# mainboard.net
KiCad netlist of a schematic drawn in EAGLE
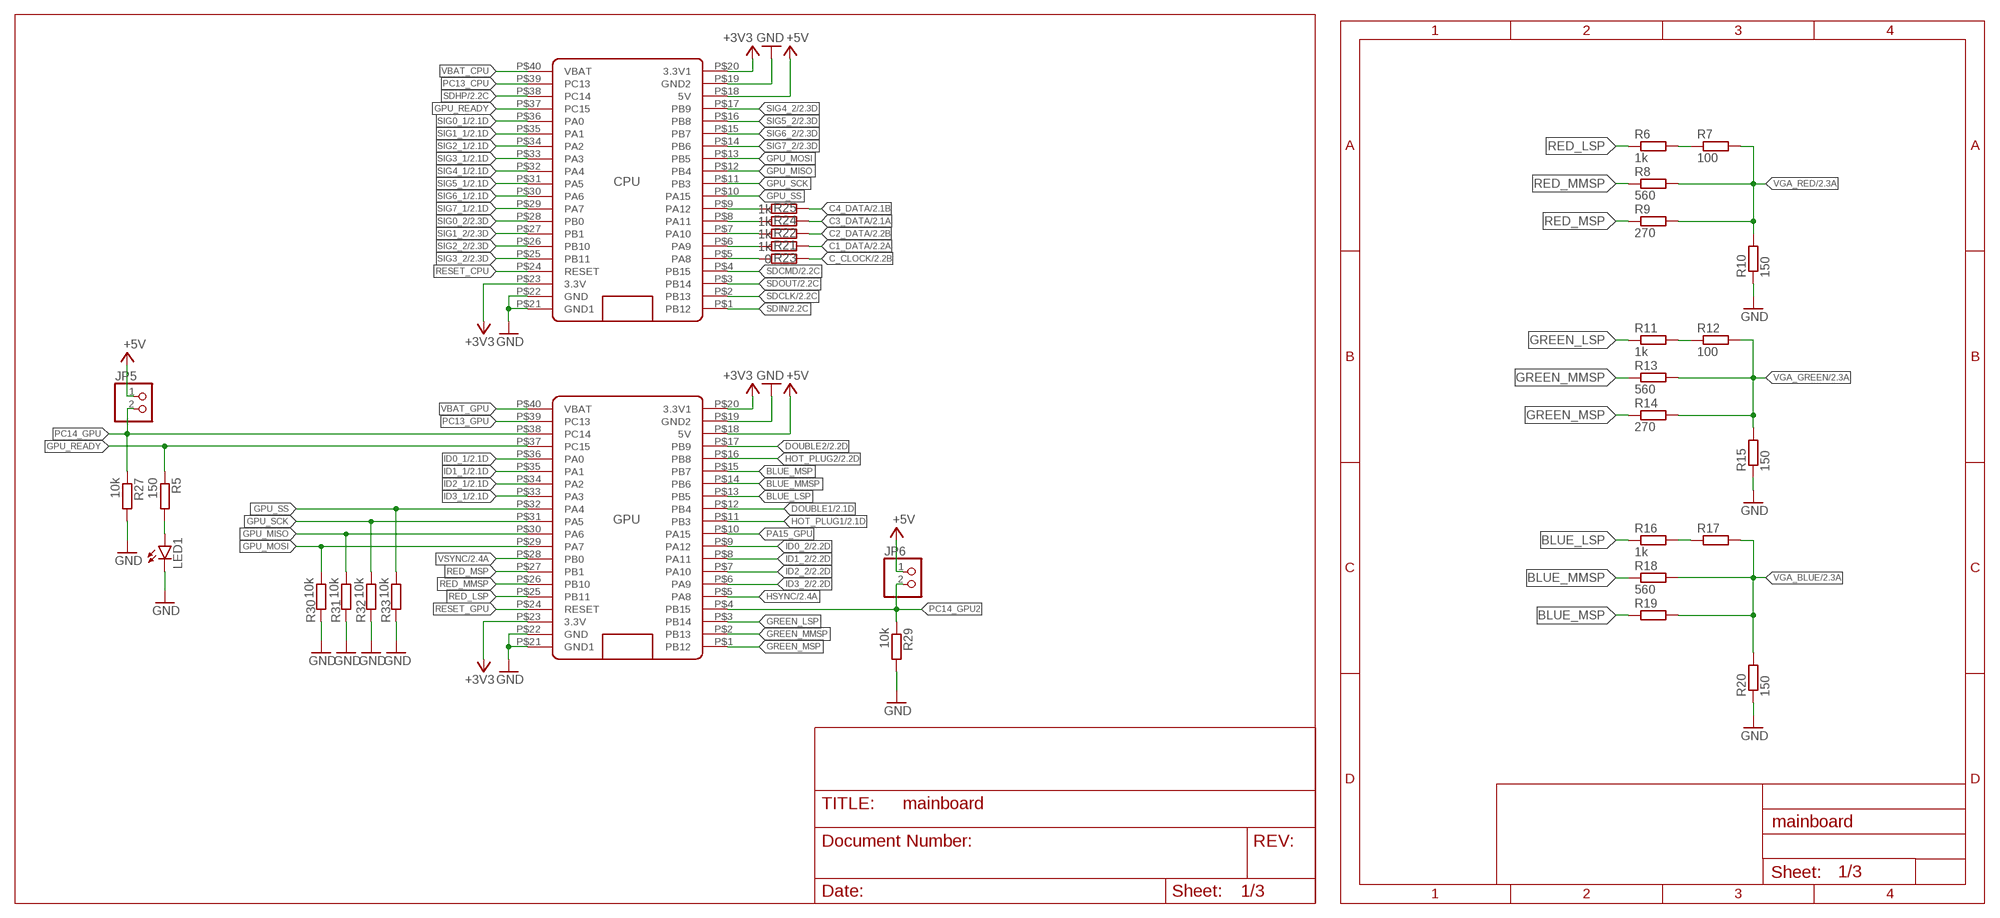
[diagram p0: schematic, sheet 1]
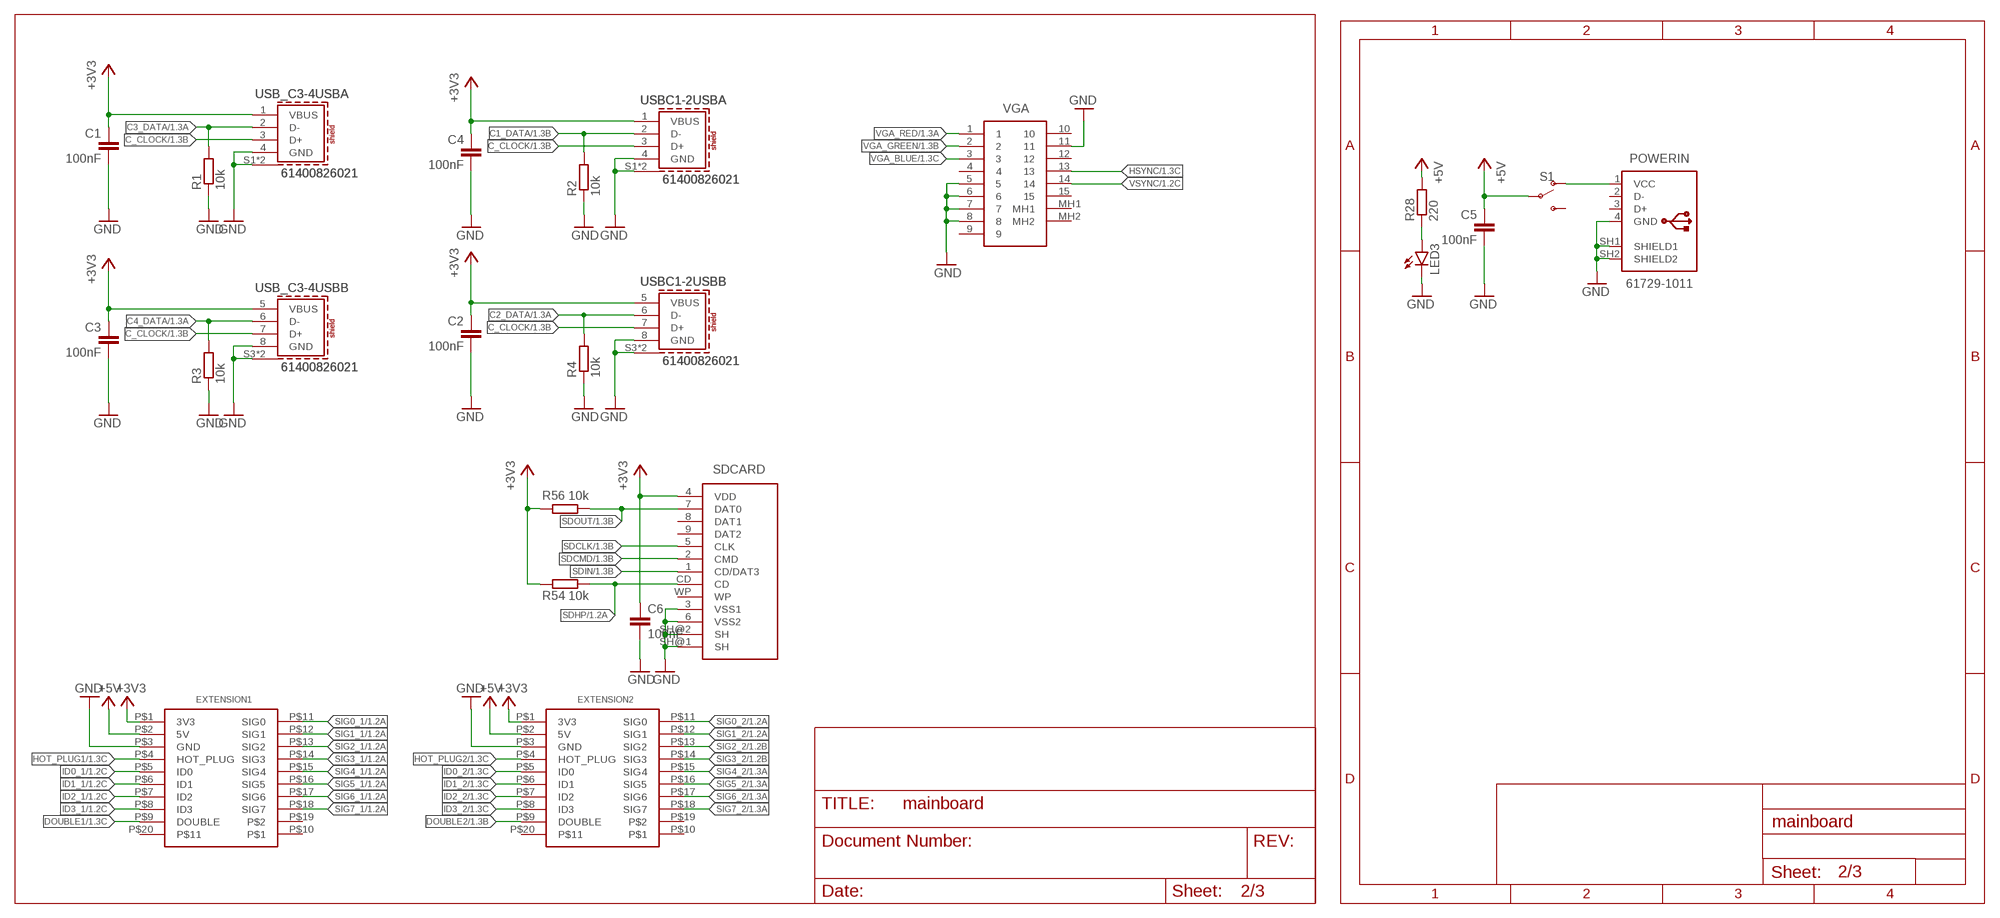
[diagram p1: schematic, sheet 2]
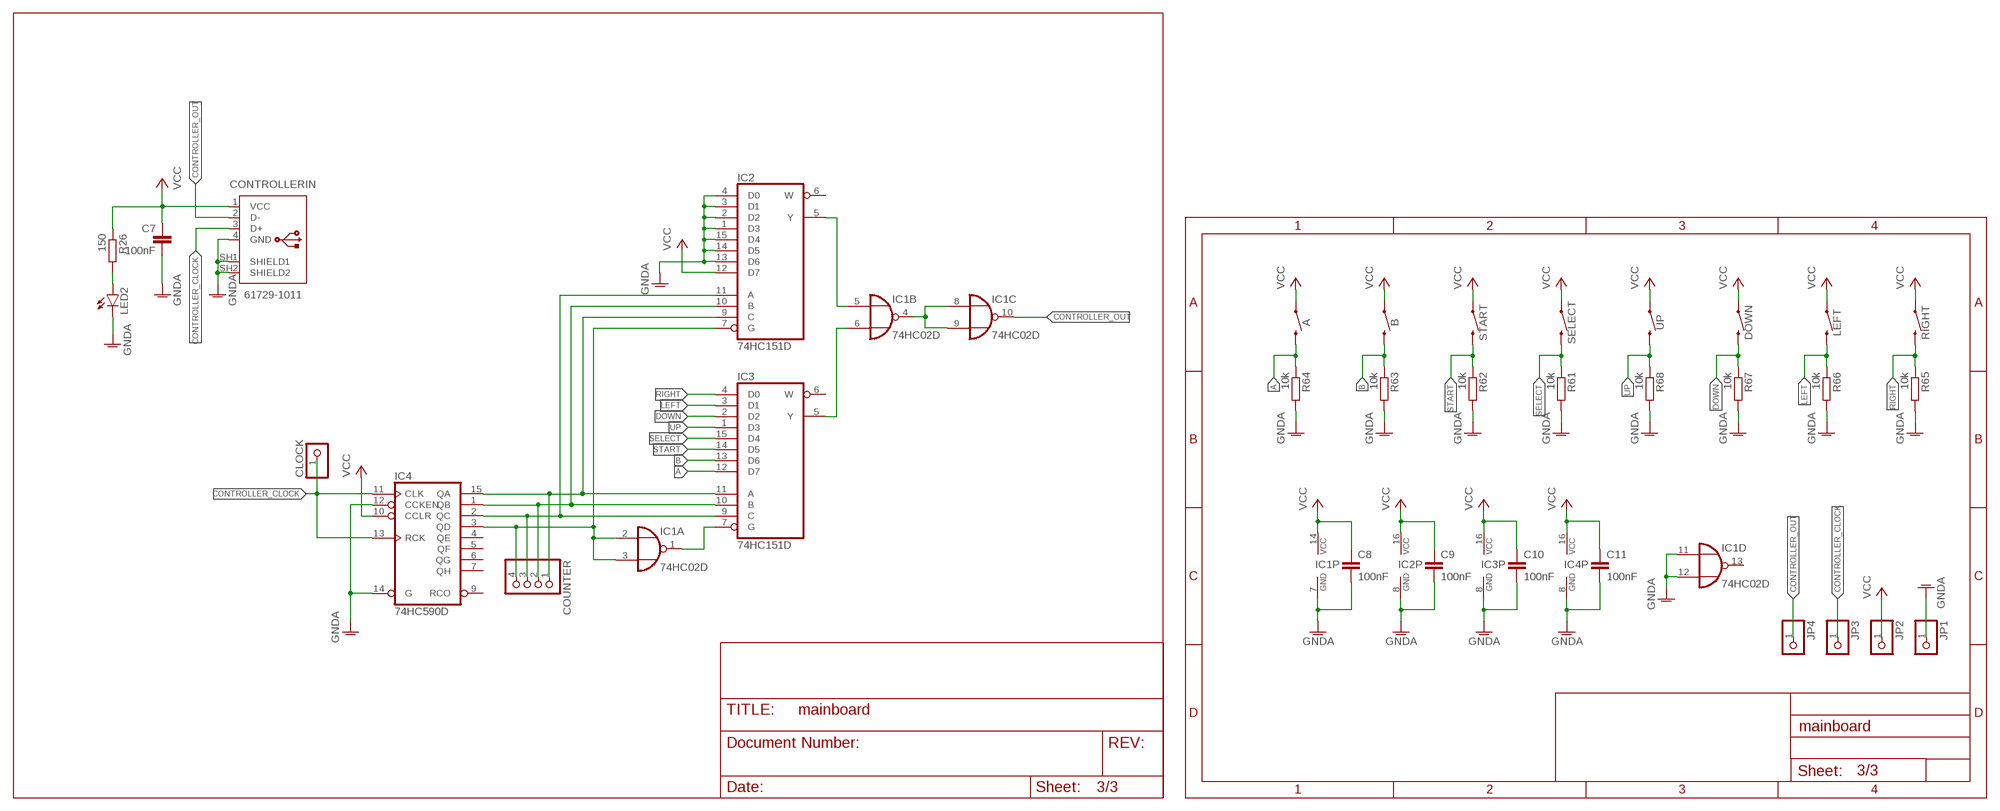
[diagram p2: schematic, sheet 3]

(export (version "E")
  (design (tool "Eeschema 10.0.6"))
  (components
    (comp (ref "C1")
      (value "100nF")
      (footprint "eagle-import:C0805")
      (libsource (lib "eagle-import") (part "C-EUC0805"))
    )
    (comp (ref "C2")
      (value "100nF")
      (footprint "eagle-import:C0805")
      (libsource (lib "eagle-import") (part "C-EUC0805"))
    )
    (comp (ref "C3")
      (value "100nF")
      (footprint "eagle-import:C0805")
      (libsource (lib "eagle-import") (part "C-EUC0805"))
    )
    (comp (ref "C4")
      (value "100nF")
      (footprint "eagle-import:C0805")
      (libsource (lib "eagle-import") (part "C-EUC0805"))
    )
    (comp (ref "C5")
      (value "100nF")
      (footprint "eagle-import:C0805")
      (libsource (lib "eagle-import") (part "C-EUC0805"))
    )
    (comp (ref "C6")
      (value "100nF")
      (footprint "eagle-import:C0805")
      (libsource (lib "eagle-import") (part "C-EUC0805"))
    )
    (comp (ref "EXTENSION1")
      (value "3511220BMSS0BNA1_2.54MM_2X20_MALE")
      (footprint "eagle-import:3511220BMSS0BNA1_2.54MM_2X20_MALE")
      (libsource (lib "eagle-import") (part "3511220BMSS0BNA1_2.54MM_2X20_MALE"))
    )
    (comp (ref "EXTENSION2")
      (value "3511220BMSS0BNA1_2.54MM_2X20_MALE")
      (footprint "eagle-import:3511220BMSS0BNA1_2.54MM_2X20_MALE")
      (libsource (lib "eagle-import") (part "3511220BMSS0BNA1_2.54MM_2X20_MALE"))
    )
    (comp (ref "LED3")
      (value "LEDCHIPLED_0805")
      (footprint "eagle-import:CHIPLED_0805")
      (libsource (lib "eagle-import") (part "LEDCHIPLED_0805"))
    )
    (comp (ref "POWERIN")
      (value "61729-1011")
      (footprint "eagle-import:61729-1011BLF")
      (fields (field (name "MANUFACTURER") "Amphenol ICC (FCI)") (field (name "MPN") "61729-1011BLF"))
      (libsource (lib "eagle-import") (part "61729-1011"))
    )
    (comp (ref "R1")
      (value "10k")
      (footprint "eagle-import:R0805")
      (libsource (lib "eagle-import") (part "R-EU_R0805"))
    )
    (comp (ref "R2")
      (value "10k")
      (footprint "eagle-import:R0805")
      (libsource (lib "eagle-import") (part "R-EU_R0805"))
    )
    (comp (ref "R3")
      (value "10k")
      (footprint "eagle-import:R0805")
      (libsource (lib "eagle-import") (part "R-EU_R0805"))
    )
    (comp (ref "R4")
      (value "10k")
      (footprint "eagle-import:R0805")
      (libsource (lib "eagle-import") (part "R-EU_R0805"))
    )
    (comp (ref "R28")
      (value "220")
      (footprint "eagle-import:R0805")
      (libsource (lib "eagle-import") (part "R-EU_R0805"))
    )
    (comp (ref "R54")
      (value "10k")
      (footprint "eagle-import:R0805")
      (libsource (lib "eagle-import") (part "R-EU_R0805"))
    )
    (comp (ref "R56")
      (value "10k")
      (footprint "eagle-import:R0805")
      (libsource (lib "eagle-import") (part "R-EU_R0805"))
    )
    (comp (ref "S1")
      (value "SWITCH-SPDT-PTH-11.6X4.0MM")
      (footprint "eagle-import:SWITCH_SPDT_PTH_11.6X4.0MM")
      (libsource (lib "eagle-import") (part "SWITCH-SPDT-PTH-11.6X4.0MM"))
    )
    (comp (ref "SD-CARD")
      (value "SD_CARD_SOCKET")
      (footprint "eagle-import:SD")
      (libsource (lib "eagle-import") (part "SD_CARD_SOCKET"))
    )
    (comp (ref "USBC1-2")
      (value "61400826021")
      (footprint "eagle-import:61400826021")
      (libsource (lib "eagle-import") (part "61400826021"))
    )
    (comp (ref "USB_C3-4")
      (value "61400826021")
      (footprint "eagle-import:61400826021")
      (libsource (lib "eagle-import") (part "61400826021"))
    )
    (comp (ref "VGA")
      (value "L77HDE15SD1CH4RHNVGA")
      (footprint "eagle-import:L77HDE15SD1CH4RHNVGA")
      (fields (field (name "MOUSER_PART_NUMBER") "523-7HDE15SDH4RHNVGA"))
      (libsource (lib "eagle-import") (part "L77HDE15SD1CH4RHNVGA"))
    )
    (comp (ref "A")
      (value "MOMENTARY-SWITCH-SPST-PTH-12MM")
      (footprint "eagle-import:TACTILE_SWITCH_PTH_12MM")
      (libsource (lib "eagle-import") (part "MOMENTARY-SWITCH-SPST-PTH-12MM"))
    )
    (comp (ref "B")
      (value "MOMENTARY-SWITCH-SPST-PTH-12MM")
      (footprint "eagle-import:TACTILE_SWITCH_PTH_12MM")
      (libsource (lib "eagle-import") (part "MOMENTARY-SWITCH-SPST-PTH-12MM"))
    )
    (comp (ref "C7")
      (value "100nF")
      (footprint "eagle-import:C0805")
      (libsource (lib "eagle-import") (part "C-EUC0805"))
    )
    (comp (ref "C8")
      (value "100nF")
      (footprint "eagle-import:C0805")
      (libsource (lib "eagle-import") (part "C-EUC0805"))
    )
    (comp (ref "C9")
      (value "100nF")
      (footprint "eagle-import:C0805")
      (libsource (lib "eagle-import") (part "C-EUC0805"))
    )
    (comp (ref "C10")
      (value "100nF")
      (footprint "eagle-import:C0805")
      (libsource (lib "eagle-import") (part "C-EUC0805"))
    )
    (comp (ref "C11")
      (value "100nF")
      (footprint "eagle-import:C0805")
      (libsource (lib "eagle-import") (part "C-EUC0805"))
    )
    (comp (ref "CLOCK")
      (value "PINHD-1X1")
      (footprint "eagle-import:1X01")
      (libsource (lib "eagle-import") (part "PINHD-1X1"))
    )
    (comp (ref "CONTROLLERIN")
      (value "61729-1011")
      (footprint "eagle-import:61729-1011BLF")
      (fields (field (name "MANUFACTURER") "Amphenol ICC (FCI)") (field (name "MPN") "61729-1011BLF"))
      (libsource (lib "eagle-import") (part "61729-1011"))
    )
    (comp (ref "COUNTER")
      (value "PINHD-1X4")
      (footprint "eagle-import:1X04")
      (libsource (lib "eagle-import") (part "PINHD-1X4"))
    )
    (comp (ref "DOWN")
      (value "MOMENTARY-SWITCH-SPST-PTH-12MM")
      (footprint "eagle-import:TACTILE_SWITCH_PTH_12MM")
      (libsource (lib "eagle-import") (part "MOMENTARY-SWITCH-SPST-PTH-12MM"))
    )
    (comp (ref "IC1")
      (value "74HC02D")
      (footprint "eagle-import:SO14")
      (libsource (lib "eagle-import") (part "7402DHC"))
    )
    (comp (ref "IC2")
      (value "74HC151D")
      (footprint "eagle-import:SO16")
      (libsource (lib "eagle-import") (part "74151DHC"))
    )
    (comp (ref "IC3")
      (value "74HC151D")
      (footprint "eagle-import:SO16")
      (libsource (lib "eagle-import") (part "74151DHC"))
    )
    (comp (ref "IC4")
      (value "74HC590D")
      (footprint "eagle-import:SO16")
      (libsource (lib "eagle-import") (part "74590DHC"))
    )
    (comp (ref "JP1")
      (value "PINHD-1X1")
      (footprint "eagle-import:1X01")
      (libsource (lib "eagle-import") (part "PINHD-1X1"))
    )
    (comp (ref "JP2")
      (value "PINHD-1X1")
      (footprint "eagle-import:1X01")
      (libsource (lib "eagle-import") (part "PINHD-1X1"))
    )
    (comp (ref "JP3")
      (value "PINHD-1X1")
      (footprint "eagle-import:1X01")
      (libsource (lib "eagle-import") (part "PINHD-1X1"))
    )
    (comp (ref "JP4")
      (value "PINHD-1X1")
      (footprint "eagle-import:1X01")
      (libsource (lib "eagle-import") (part "PINHD-1X1"))
    )
    (comp (ref "LED2")
      (value "LEDCHIPLED_0805")
      (footprint "eagle-import:CHIPLED_0805")
      (libsource (lib "eagle-import") (part "LEDCHIPLED_0805"))
    )
    (comp (ref "LEFT")
      (value "MOMENTARY-SWITCH-SPST-PTH-12MM")
      (footprint "eagle-import:TACTILE_SWITCH_PTH_12MM")
      (libsource (lib "eagle-import") (part "MOMENTARY-SWITCH-SPST-PTH-12MM"))
    )
    (comp (ref "R26")
      (value "150")
      (footprint "eagle-import:R0805")
      (libsource (lib "eagle-import") (part "R-EU_R0805"))
    )
    (comp (ref "R61")
      (value "10k")
      (footprint "eagle-import:R0805")
      (libsource (lib "eagle-import") (part "R-EU_R0805"))
    )
    (comp (ref "R62")
      (value "10k")
      (footprint "eagle-import:R0805")
      (libsource (lib "eagle-import") (part "R-EU_R0805"))
    )
    (comp (ref "R63")
      (value "10k")
      (footprint "eagle-import:R0805")
      (libsource (lib "eagle-import") (part "R-EU_R0805"))
    )
    (comp (ref "R64")
      (value "10k")
      (footprint "eagle-import:R0805")
      (libsource (lib "eagle-import") (part "R-EU_R0805"))
    )
    (comp (ref "R65")
      (value "10k")
      (footprint "eagle-import:R0805")
      (libsource (lib "eagle-import") (part "R-EU_R0805"))
    )
    (comp (ref "R66")
      (value "10k")
      (footprint "eagle-import:R0805")
      (libsource (lib "eagle-import") (part "R-EU_R0805"))
    )
    (comp (ref "R67")
      (value "10k")
      (footprint "eagle-import:R0805")
      (libsource (lib "eagle-import") (part "R-EU_R0805"))
    )
    (comp (ref "R68")
      (value "10k")
      (footprint "eagle-import:R0805")
      (libsource (lib "eagle-import") (part "R-EU_R0805"))
    )
    (comp (ref "RIGHT")
      (value "MOMENTARY-SWITCH-SPST-PTH-12MM")
      (footprint "eagle-import:TACTILE_SWITCH_PTH_12MM")
      (libsource (lib "eagle-import") (part "MOMENTARY-SWITCH-SPST-PTH-12MM"))
    )
    (comp (ref "SELECT")
      (value "MOMENTARY-SWITCH-SPST-PTH-12MM")
      (footprint "eagle-import:TACTILE_SWITCH_PTH_12MM")
      (libsource (lib "eagle-import") (part "MOMENTARY-SWITCH-SPST-PTH-12MM"))
    )
    (comp (ref "START")
      (value "MOMENTARY-SWITCH-SPST-PTH-12MM")
      (footprint "eagle-import:TACTILE_SWITCH_PTH_12MM")
      (libsource (lib "eagle-import") (part "MOMENTARY-SWITCH-SPST-PTH-12MM"))
    )
    (comp (ref "UP")
      (value "MOMENTARY-SWITCH-SPST-PTH-12MM")
      (footprint "eagle-import:TACTILE_SWITCH_PTH_12MM")
      (libsource (lib "eagle-import") (part "MOMENTARY-SWITCH-SPST-PTH-12MM"))
    )
    (comp (ref "CPU")
      (value "BLUE_PILLADVANCED")
      (footprint "eagle-import:BLUE_PILL_ADV")
      (libsource (lib "eagle-import") (part "BLUE_PILLADVANCED"))
    )
    (comp (ref "GPU")
      (value "BLUE_PILLADVANCED")
      (footprint "eagle-import:BLUE_PILL_ADV")
      (libsource (lib "eagle-import") (part "BLUE_PILLADVANCED"))
    )
    (comp (ref "JP5")
      (value "PINHD-1X2")
      (footprint "eagle-import:1X02")
      (libsource (lib "eagle-import") (part "PINHD-1X2"))
    )
    (comp (ref "JP6")
      (value "PINHD-1X2")
      (footprint "eagle-import:1X02")
      (libsource (lib "eagle-import") (part "PINHD-1X2"))
    )
    (comp (ref "LED1")
      (value "LEDCHIPLED_0805")
      (footprint "eagle-import:CHIPLED_0805")
      (libsource (lib "eagle-import") (part "LEDCHIPLED_0805"))
    )
    (comp (ref "R5")
      (value "150")
      (footprint "eagle-import:R0805")
      (libsource (lib "eagle-import") (part "R-EU_R0805"))
    )
    (comp (ref "R6")
      (value "1k")
      (footprint "eagle-import:R0805")
      (libsource (lib "eagle-import") (part "R-EU_R0805"))
    )
    (comp (ref "R7")
      (value "100")
      (footprint "eagle-import:R0805")
      (libsource (lib "eagle-import") (part "R-EU_R0805"))
    )
    (comp (ref "R8")
      (value "560")
      (footprint "eagle-import:R0805")
      (libsource (lib "eagle-import") (part "R-EU_R0805"))
    )
    (comp (ref "R9")
      (value "270")
      (footprint "eagle-import:R0805")
      (libsource (lib "eagle-import") (part "R-EU_R0805"))
    )
    (comp (ref "R10")
      (value "150")
      (footprint "eagle-import:R0805")
      (libsource (lib "eagle-import") (part "R-EU_R0805"))
    )
    (comp (ref "R11")
      (value "1k")
      (footprint "eagle-import:R0805")
      (libsource (lib "eagle-import") (part "R-EU_R0805"))
    )
    (comp (ref "R12")
      (value "100")
      (footprint "eagle-import:R0805")
      (libsource (lib "eagle-import") (part "R-EU_R0805"))
    )
    (comp (ref "R13")
      (value "560")
      (footprint "eagle-import:R0805")
      (libsource (lib "eagle-import") (part "R-EU_R0805"))
    )
    (comp (ref "R14")
      (value "270")
      (footprint "eagle-import:R0805")
      (libsource (lib "eagle-import") (part "R-EU_R0805"))
    )
    (comp (ref "R15")
      (value "150")
      (footprint "eagle-import:R0805")
      (libsource (lib "eagle-import") (part "R-EU_R0805"))
    )
    (comp (ref "R16")
      (value "1k")
      (footprint "eagle-import:R0805")
      (libsource (lib "eagle-import") (part "R-EU_R0805"))
    )
    (comp (ref "R17")
      (value "100")
      (footprint "eagle-import:R0805")
      (libsource (lib "eagle-import") (part "R-EU_R0805"))
    )
    (comp (ref "R18")
      (value "560")
      (footprint "eagle-import:R0805")
      (libsource (lib "eagle-import") (part "R-EU_R0805"))
    )
    (comp (ref "R19")
      (value "270")
      (footprint "eagle-import:R0805")
      (libsource (lib "eagle-import") (part "R-EU_R0805"))
    )
    (comp (ref "R20")
      (value "150")
      (footprint "eagle-import:R0805")
      (libsource (lib "eagle-import") (part "R-EU_R0805"))
    )
    (comp (ref "R21")
      (value "1k")
      (footprint "eagle-import:R0805")
      (libsource (lib "eagle-import") (part "R-EU_R0805"))
    )
    (comp (ref "R22")
      (value "1k")
      (footprint "eagle-import:R0805")
      (libsource (lib "eagle-import") (part "R-EU_R0805"))
    )
    (comp (ref "R23")
      (value "0")
      (footprint "eagle-import:R0805")
      (libsource (lib "eagle-import") (part "R-EU_R0805"))
    )
    (comp (ref "R24")
      (value "1k")
      (footprint "eagle-import:R0805")
      (libsource (lib "eagle-import") (part "R-EU_R0805"))
    )
    (comp (ref "R25")
      (value "1k")
      (footprint "eagle-import:R0805")
      (libsource (lib "eagle-import") (part "R-EU_R0805"))
    )
    (comp (ref "R27")
      (value "10k")
      (footprint "eagle-import:R0805")
      (libsource (lib "eagle-import") (part "R-EU_R0805"))
    )
    (comp (ref "R29")
      (value "10k")
      (footprint "eagle-import:R0805")
      (libsource (lib "eagle-import") (part "R-EU_R0805"))
    )
    (comp (ref "R30")
      (value "10k")
      (footprint "eagle-import:R0805")
      (libsource (lib "eagle-import") (part "R-EU_R0805"))
    )
    (comp (ref "R31")
      (value "10k")
      (footprint "eagle-import:R0805")
      (libsource (lib "eagle-import") (part "R-EU_R0805"))
    )
    (comp (ref "R32")
      (value "10k")
      (footprint "eagle-import:R0805")
      (libsource (lib "eagle-import") (part "R-EU_R0805"))
    )
    (comp (ref "R33")
      (value "10k")
      (footprint "eagle-import:R0805")
      (libsource (lib "eagle-import") (part "R-EU_R0805"))
    )
  )
  (nets
    (net (code "1") (name "+3V3") (class "Default")
      (node (ref "C1") (pin "1") (pinfunction "1_1") (pintype "passive"))
      (node (ref "C2") (pin "1") (pinfunction "1_1") (pintype "passive"))
      (node (ref "C3") (pin "1") (pinfunction "1_1") (pintype "passive"))
      (node (ref "C4") (pin "1") (pinfunction "1_1") (pintype "passive"))
      (node (ref "C6") (pin "1") (pinfunction "1_1") (pintype "passive"))
      (node (ref "CPU") (pin "P$20") (pinfunction "3.3V1_P$20") (pintype "bidirectional"))
      (node (ref "CPU") (pin "P$23") (pinfunction "3.3V_P$23") (pintype "bidirectional"))
      (node (ref "EXTENSION1") (pin "P$1") (pinfunction "3V3_P$1") (pintype "bidirectional"))
      (node (ref "EXTENSION2") (pin "P$1") (pinfunction "3V3_P$1") (pintype "bidirectional"))
      (node (ref "GPU") (pin "P$20") (pinfunction "3.3V1_P$20") (pintype "bidirectional"))
      (node (ref "GPU") (pin "P$23") (pinfunction "3.3V_P$23") (pintype "bidirectional"))
      (node (ref "R54") (pin "2") (pinfunction "2_2") (pintype "passive"))
      (node (ref "R56") (pin "2") (pinfunction "2_2") (pintype "passive"))
      (node (ref "SD-CARD") (pin "4") (pinfunction "VDD_4") (pintype "power_in"))
      (node (ref "USBC1-2") (pin "1") (pinfunction "VBUS_1") (pintype "passive"))
      (node (ref "USBC1-2") (pin "5") (pinfunction "VBUS_5") (pintype "passive"))
      (node (ref "USB_C3-4") (pin "1") (pinfunction "VBUS_1") (pintype "passive"))
      (node (ref "USB_C3-4") (pin "5") (pinfunction "VBUS_5") (pintype "passive"))
    )
    (net (code "2") (name "+5V") (class "Default")
      (node (ref "C5") (pin "1") (pinfunction "1_1") (pintype "passive"))
      (node (ref "CPU") (pin "P$18") (pinfunction "5V_P$18") (pintype "bidirectional"))
      (node (ref "EXTENSION1") (pin "P$2") (pinfunction "5V_P$2") (pintype "bidirectional"))
      (node (ref "EXTENSION2") (pin "P$2") (pinfunction "5V_P$2") (pintype "bidirectional"))
      (node (ref "GPU") (pin "P$18") (pinfunction "5V_P$18") (pintype "bidirectional"))
      (node (ref "JP5") (pin "1") (pinfunction "1_1") (pintype "passive"))
      (node (ref "JP6") (pin "1") (pinfunction "1_1") (pintype "passive"))
      (node (ref "R28") (pin "2") (pinfunction "2_2") (pintype "passive"))
      (node (ref "S1") (pin "2") (pinfunction "P_2") (pintype "passive"))
    )
    (net (code "3") (name "A") (class "Default")
      (node (ref "A") (pin "3") (pinfunction "2_3") (pintype "passive"))
      (node (ref "IC3") (pin "12") (pinfunction "D7_12") (pintype "input"))
      (node (ref "R64") (pin "1") (pinfunction "1_1") (pintype "passive"))
    )
    (net (code "4") (name "B") (class "Default")
      (node (ref "B") (pin "3") (pinfunction "2_3") (pintype "passive"))
      (node (ref "IC3") (pin "13") (pinfunction "D6_13") (pintype "input"))
      (node (ref "R63") (pin "1") (pinfunction "1_1") (pintype "passive"))
    )
    (net (code "5") (name "BLUE_LSP") (class "Default")
      (node (ref "GPU") (pin "P$13") (pinfunction "PB5_P$13") (pintype "bidirectional"))
      (node (ref "R16") (pin "1") (pinfunction "1_1") (pintype "passive"))
    )
    (net (code "6") (name "BLUE_MMSP") (class "Default")
      (node (ref "GPU") (pin "P$14") (pinfunction "PB6_P$14") (pintype "bidirectional"))
      (node (ref "R18") (pin "1") (pinfunction "1_1") (pintype "passive"))
    )
    (net (code "7") (name "BLUE_MSP") (class "Default")
      (node (ref "GPU") (pin "P$15") (pinfunction "PB7_P$15") (pintype "bidirectional"))
      (node (ref "R19") (pin "1") (pinfunction "1_1") (pintype "passive"))
    )
    (net (code "8") (name "C1_DATA") (class "Default")
      (node (ref "R2") (pin "2") (pinfunction "2_2") (pintype "passive"))
      (node (ref "R21") (pin "1") (pinfunction "1_1") (pintype "passive"))
      (node (ref "USBC1-2") (pin "2") (pinfunction "D-_2") (pintype "passive"))
    )
    (net (code "9") (name "C2_DATA") (class "Default")
      (node (ref "R22") (pin "1") (pinfunction "1_1") (pintype "passive"))
      (node (ref "R4") (pin "2") (pinfunction "2_2") (pintype "passive"))
      (node (ref "USBC1-2") (pin "6") (pinfunction "D-_6") (pintype "passive"))
    )
    (net (code "10") (name "C3_DATA") (class "Default")
      (node (ref "R1") (pin "2") (pinfunction "2_2") (pintype "passive"))
      (node (ref "R24") (pin "1") (pinfunction "1_1") (pintype "passive"))
      (node (ref "USB_C3-4") (pin "2") (pinfunction "D-_2") (pintype "passive"))
    )
    (net (code "11") (name "C4_DATA") (class "Default")
      (node (ref "R25") (pin "1") (pinfunction "1_1") (pintype "passive"))
      (node (ref "R3") (pin "2") (pinfunction "2_2") (pintype "passive"))
      (node (ref "USB_C3-4") (pin "6") (pinfunction "D-_6") (pintype "passive"))
    )
    (net (code "12") (name "CONTROLLER_CLOCK") (class "Default")
      (node (ref "CLOCK") (pin "1") (pinfunction "1_1") (pintype "passive"))
      (node (ref "CONTROLLERIN") (pin "3") (pinfunction "D+_3") (pintype "bidirectional"))
      (node (ref "IC4") (pin "11") (pinfunction "CLK_11") (pintype "input"))
      (node (ref "IC4") (pin "13") (pinfunction "RCK_13") (pintype "input"))
      (node (ref "JP3") (pin "1") (pinfunction "1_1") (pintype "passive"))
    )
    (net (code "13") (name "CONTROLLER_OUT") (class "Default")
      (node (ref "CONTROLLERIN") (pin "2") (pinfunction "D-_2") (pintype "bidirectional"))
      (node (ref "IC1") (pin "10") (pinfunction "O_10") (pintype "output"))
      (node (ref "JP4") (pin "1") (pinfunction "1_1") (pintype "passive"))
    )
    (net (code "14") (name "C_CLOCK") (class "Default")
      (node (ref "R23") (pin "1") (pinfunction "1_1") (pintype "passive"))
      (node (ref "USBC1-2") (pin "3") (pinfunction "D+_3") (pintype "passive"))
      (node (ref "USBC1-2") (pin "7") (pinfunction "D+_7") (pintype "passive"))
      (node (ref "USB_C3-4") (pin "3") (pinfunction "D+_3") (pintype "passive"))
      (node (ref "USB_C3-4") (pin "7") (pinfunction "D+_7") (pintype "passive"))
    )
    (net (code "15") (name "DOUBLE1") (class "Default")
      (node (ref "EXTENSION1") (pin "P$9") (pinfunction "DOUBLE_P$9") (pintype "bidirectional"))
      (node (ref "GPU") (pin "P$12") (pinfunction "PB4_P$12") (pintype "bidirectional"))
    )
    (net (code "16") (name "DOUBLE2") (class "Default")
      (node (ref "EXTENSION2") (pin "P$9") (pinfunction "DOUBLE_P$9") (pintype "bidirectional"))
      (node (ref "GPU") (pin "P$17") (pinfunction "PB9_P$17") (pintype "bidirectional"))
    )
    (net (code "17") (name "DOWN") (class "Default")
      (node (ref "DOWN") (pin "3") (pinfunction "2_3") (pintype "passive"))
      (node (ref "IC3") (pin "2") (pinfunction "D2_2") (pintype "input"))
      (node (ref "R67") (pin "1") (pinfunction "1_1") (pintype "passive"))
    )
    (net (code "18") (name "GND") (class "Default")
      (node (ref "C1") (pin "2") (pinfunction "2_2") (pintype "passive"))
      (node (ref "C2") (pin "2") (pinfunction "2_2") (pintype "passive"))
      (node (ref "C3") (pin "2") (pinfunction "2_2") (pintype "passive"))
      (node (ref "C4") (pin "2") (pinfunction "2_2") (pintype "passive"))
      (node (ref "C5") (pin "2") (pinfunction "2_2") (pintype "passive"))
      (node (ref "C6") (pin "2") (pinfunction "2_2") (pintype "passive"))
      (node (ref "CPU") (pin "P$19") (pinfunction "GND2_P$19") (pintype "bidirectional"))
      (node (ref "CPU") (pin "P$21") (pinfunction "GND1_P$21") (pintype "power_in"))
      (node (ref "CPU") (pin "P$22") (pinfunction "GND_P$22") (pintype "bidirectional"))
      (node (ref "EXTENSION1") (pin "P$3") (pinfunction "GND_P$3") (pintype "bidirectional"))
      (node (ref "EXTENSION2") (pin "P$3") (pinfunction "GND_P$3") (pintype "bidirectional"))
      (node (ref "GPU") (pin "P$19") (pinfunction "GND2_P$19") (pintype "bidirectional"))
      (node (ref "GPU") (pin "P$21") (pinfunction "GND1_P$21") (pintype "power_in"))
      (node (ref "GPU") (pin "P$22") (pinfunction "GND_P$22") (pintype "bidirectional"))
      (node (ref "LED1") (pin "C") (pinfunction "C_C") (pintype "passive"))
      (node (ref "LED3") (pin "C") (pinfunction "C_C") (pintype "passive"))
      (node (ref "POWERIN") (pin "4") (pinfunction "GND_4") (pintype "power_in"))
      (node (ref "POWERIN") (pin "SH1") (pinfunction "SHIELD1_SH1") (pintype "power_in"))
      (node (ref "POWERIN") (pin "SH2") (pinfunction "SHIELD2_SH2") (pintype "power_in"))
      (node (ref "R1") (pin "1") (pinfunction "1_1") (pintype "passive"))
      (node (ref "R10") (pin "1") (pinfunction "1_1") (pintype "passive"))
      (node (ref "R15") (pin "1") (pinfunction "1_1") (pintype "passive"))
      (node (ref "R2") (pin "1") (pinfunction "1_1") (pintype "passive"))
      (node (ref "R20") (pin "1") (pinfunction "1_1") (pintype "passive"))
      (node (ref "R27") (pin "2") (pinfunction "2_2") (pintype "passive"))
      (node (ref "R29") (pin "2") (pinfunction "2_2") (pintype "passive"))
      (node (ref "R3") (pin "1") (pinfunction "1_1") (pintype "passive"))
      (node (ref "R30") (pin "2") (pinfunction "2_2") (pintype "passive"))
      (node (ref "R31") (pin "2") (pinfunction "2_2") (pintype "passive"))
      (node (ref "R32") (pin "2") (pinfunction "2_2") (pintype "passive"))
      (node (ref "R33") (pin "2") (pinfunction "2_2") (pintype "passive"))
      (node (ref "R4") (pin "1") (pinfunction "1_1") (pintype "passive"))
      (node (ref "SD-CARD") (pin "3") (pinfunction "VSS1_3") (pintype "power_in"))
      (node (ref "SD-CARD") (pin "6") (pinfunction "VSS2_6") (pintype "power_in"))
      (node (ref "SD-CARD") (pin "SH@1") (pinfunction "SH_SH@1") (pintype "bidirectional"))
      (node (ref "SD-CARD") (pin "SH@2") (pinfunction "SH_SH@2") (pintype "bidirectional"))
      (node (ref "USBC1-2") (pin "4") (pinfunction "GND_4") (pintype "passive"))
      (node (ref "USBC1-2") (pin "8") (pinfunction "GND_8") (pintype "passive"))
      (node (ref "USBC1-2") (pin "S1") (pinfunction "SHIELD_S1") (pintype "passive"))
      (node (ref "USBC1-2") (pin "S2") (pinfunction "SHIELD_S2") (pintype "passive"))
      (node (ref "USBC1-2") (pin "S3") (pinfunction "SHIELD_S3") (pintype "passive"))
      (node (ref "USBC1-2") (pin "S4") (pinfunction "SHIELD_S4") (pintype "passive"))
      (node (ref "USB_C3-4") (pin "4") (pinfunction "GND_4") (pintype "passive"))
      (node (ref "USB_C3-4") (pin "8") (pinfunction "GND_8") (pintype "passive"))
      (node (ref "USB_C3-4") (pin "S1") (pinfunction "SHIELD_S1") (pintype "passive"))
      (node (ref "USB_C3-4") (pin "S2") (pinfunction "SHIELD_S2") (pintype "passive"))
      (node (ref "USB_C3-4") (pin "S3") (pinfunction "SHIELD_S3") (pintype "passive"))
      (node (ref "USB_C3-4") (pin "S4") (pinfunction "SHIELD_S4") (pintype "passive"))
      (node (ref "VGA") (pin "11") (pinfunction "11_11") (pintype "bidirectional"))
      (node (ref "VGA") (pin "5") (pinfunction "5_5") (pintype "bidirectional"))
      (node (ref "VGA") (pin "6") (pinfunction "6_6") (pintype "bidirectional"))
      (node (ref "VGA") (pin "7") (pinfunction "7_7") (pintype "bidirectional"))
      (node (ref "VGA") (pin "8") (pinfunction "8_8") (pintype "bidirectional"))
    )
    (net (code "19") (name "GNDA") (class "Default")
      (node (ref "C10") (pin "2") (pinfunction "2_2") (pintype "passive"))
      (node (ref "C11") (pin "2") (pinfunction "2_2") (pintype "passive"))
      (node (ref "C7") (pin "2") (pinfunction "2_2") (pintype "passive"))
      (node (ref "C8") (pin "2") (pinfunction "2_2") (pintype "passive"))
      (node (ref "C9") (pin "2") (pinfunction "2_2") (pintype "passive"))
      (node (ref "CONTROLLERIN") (pin "4") (pinfunction "GND_4") (pintype "power_in"))
      (node (ref "CONTROLLERIN") (pin "SH1") (pinfunction "SHIELD1_SH1") (pintype "power_in"))
      (node (ref "CONTROLLERIN") (pin "SH2") (pinfunction "SHIELD2_SH2") (pintype "power_in"))
      (node (ref "IC1") (pin "11") (pinfunction "I0_11") (pintype "input"))
      (node (ref "IC1") (pin "12") (pinfunction "I1_12") (pintype "input"))
      (node (ref "IC1") (pin "7") (pinfunction "GND_7") (pintype "power_in"))
      (node (ref "IC2") (pin "1") (pinfunction "D3_1") (pintype "input"))
      (node (ref "IC2") (pin "13") (pinfunction "D6_13") (pintype "input"))
      (node (ref "IC2") (pin "14") (pinfunction "D5_14") (pintype "input"))
      (node (ref "IC2") (pin "15") (pinfunction "D4_15") (pintype "input"))
      (node (ref "IC2") (pin "2") (pinfunction "D2_2") (pintype "input"))
      (node (ref "IC2") (pin "3") (pinfunction "D1_3") (pintype "input"))
      (node (ref "IC2") (pin "4") (pinfunction "D0_4") (pintype "input"))
      (node (ref "IC2") (pin "8") (pinfunction "GND_8") (pintype "power_in"))
      (node (ref "IC3") (pin "8") (pinfunction "GND_8") (pintype "power_in"))
      (node (ref "IC4") (pin "12") (pinfunction "CCKEN_12") (pintype "input"))
      (node (ref "IC4") (pin "14") (pinfunction "G_14") (pintype "input"))
      (node (ref "IC4") (pin "8") (pinfunction "GND_8") (pintype "power_in"))
      (node (ref "JP1") (pin "1") (pinfunction "1_1") (pintype "passive"))
      (node (ref "LED2") (pin "C") (pinfunction "C_C") (pintype "passive"))
      (node (ref "R61") (pin "2") (pinfunction "2_2") (pintype "passive"))
      (node (ref "R62") (pin "2") (pinfunction "2_2") (pintype "passive"))
      (node (ref "R63") (pin "2") (pinfunction "2_2") (pintype "passive"))
      (node (ref "R64") (pin "2") (pinfunction "2_2") (pintype "passive"))
      (node (ref "R65") (pin "2") (pinfunction "2_2") (pintype "passive"))
      (node (ref "R66") (pin "2") (pinfunction "2_2") (pintype "passive"))
      (node (ref "R67") (pin "2") (pinfunction "2_2") (pintype "passive"))
      (node (ref "R68") (pin "2") (pinfunction "2_2") (pintype "passive"))
    )
    (net (code "20") (name "GPU_MISO") (class "Default")
      (node (ref "CPU") (pin "P$12") (pinfunction "PB4_P$12") (pintype "bidirectional"))
      (node (ref "GPU") (pin "P$30") (pinfunction "PA6_P$30") (pintype "bidirectional"))
      (node (ref "R31") (pin "1") (pinfunction "1_1") (pintype "passive"))
    )
    (net (code "21") (name "GPU_MOSI") (class "Default")
      (node (ref "CPU") (pin "P$13") (pinfunction "PB5_P$13") (pintype "bidirectional"))
      (node (ref "GPU") (pin "P$29") (pinfunction "PA7_P$29") (pintype "bidirectional"))
      (node (ref "R30") (pin "1") (pinfunction "1_1") (pintype "passive"))
    )
    (net (code "22") (name "GPU_READY") (class "Default")
      (node (ref "CPU") (pin "P$37") (pinfunction "PC15_P$37") (pintype "bidirectional"))
      (node (ref "GPU") (pin "P$37") (pinfunction "PC15_P$37") (pintype "bidirectional"))
      (node (ref "R5") (pin "1") (pinfunction "1_1") (pintype "passive"))
    )
    (net (code "23") (name "GPU_SCK") (class "Default")
      (node (ref "CPU") (pin "P$11") (pinfunction "PB3_P$11") (pintype "bidirectional"))
      (node (ref "GPU") (pin "P$31") (pinfunction "PA5_P$31") (pintype "bidirectional"))
      (node (ref "R32") (pin "1") (pinfunction "1_1") (pintype "passive"))
    )
    (net (code "24") (name "GPU_SS") (class "Default")
      (node (ref "CPU") (pin "P$10") (pinfunction "PA15_P$10") (pintype "bidirectional"))
      (node (ref "GPU") (pin "P$32") (pinfunction "PA4_P$32") (pintype "bidirectional"))
      (node (ref "R33") (pin "1") (pinfunction "1_1") (pintype "passive"))
    )
    (net (code "25") (name "GREEN_LSP") (class "Default")
      (node (ref "GPU") (pin "P$3") (pinfunction "PB14_P$3") (pintype "bidirectional"))
      (node (ref "R11") (pin "1") (pinfunction "1_1") (pintype "passive"))
    )
    (net (code "26") (name "GREEN_MMSP") (class "Default")
      (node (ref "GPU") (pin "P$2") (pinfunction "PB13_P$2") (pintype "bidirectional"))
      (node (ref "R13") (pin "1") (pinfunction "1_1") (pintype "passive"))
    )
    (net (code "27") (name "GREEN_MSP") (class "Default")
      (node (ref "GPU") (pin "P$1") (pinfunction "PB12_P$1") (pintype "bidirectional"))
      (node (ref "R14") (pin "1") (pinfunction "1_1") (pintype "passive"))
    )
    (net (code "28") (name "HOT_PLUG1") (class "Default")
      (node (ref "EXTENSION1") (pin "P$4") (pinfunction "HOT_PLUG_P$4") (pintype "bidirectional"))
      (node (ref "GPU") (pin "P$11") (pinfunction "PB3_P$11") (pintype "bidirectional"))
    )
    (net (code "29") (name "HOT_PLUG2") (class "Default")
      (node (ref "EXTENSION2") (pin "P$4") (pinfunction "HOT_PLUG_P$4") (pintype "bidirectional"))
      (node (ref "GPU") (pin "P$16") (pinfunction "PB8_P$16") (pintype "bidirectional"))
    )
    (net (code "30") (name "HSYNC") (class "Default")
      (node (ref "GPU") (pin "P$5") (pinfunction "PA8_P$5") (pintype "bidirectional"))
      (node (ref "VGA") (pin "13") (pinfunction "13_13") (pintype "bidirectional"))
    )
    (net (code "31") (name "ID0_1") (class "Default")
      (node (ref "EXTENSION1") (pin "P$5") (pinfunction "ID0_P$5") (pintype "bidirectional"))
      (node (ref "GPU") (pin "P$36") (pinfunction "PA0_P$36") (pintype "bidirectional"))
    )
    (net (code "32") (name "ID0_2") (class "Default")
      (node (ref "EXTENSION2") (pin "P$5") (pinfunction "ID0_P$5") (pintype "bidirectional"))
      (node (ref "GPU") (pin "P$9") (pinfunction "PA12_P$9") (pintype "bidirectional"))
    )
    (net (code "33") (name "ID1_1") (class "Default")
      (node (ref "EXTENSION1") (pin "P$6") (pinfunction "ID1_P$6") (pintype "bidirectional"))
      (node (ref "GPU") (pin "P$35") (pinfunction "PA1_P$35") (pintype "bidirectional"))
    )
    (net (code "34") (name "ID1_2") (class "Default")
      (node (ref "EXTENSION2") (pin "P$6") (pinfunction "ID1_P$6") (pintype "bidirectional"))
      (node (ref "GPU") (pin "P$8") (pinfunction "PA11_P$8") (pintype "bidirectional"))
    )
    (net (code "35") (name "ID2_1") (class "Default")
      (node (ref "EXTENSION1") (pin "P$7") (pinfunction "ID2_P$7") (pintype "bidirectional"))
      (node (ref "GPU") (pin "P$34") (pinfunction "PA2_P$34") (pintype "bidirectional"))
    )
    (net (code "36") (name "ID2_2") (class "Default")
      (node (ref "EXTENSION2") (pin "P$7") (pinfunction "ID2_P$7") (pintype "bidirectional"))
      (node (ref "GPU") (pin "P$7") (pinfunction "PA10_P$7") (pintype "bidirectional"))
    )
    (net (code "37") (name "ID3_1") (class "Default")
      (node (ref "EXTENSION1") (pin "P$8") (pinfunction "ID3_P$8") (pintype "bidirectional"))
      (node (ref "GPU") (pin "P$33") (pinfunction "PA3_P$33") (pintype "bidirectional"))
    )
    (net (code "38") (name "ID3_2") (class "Default")
      (node (ref "EXTENSION2") (pin "P$8") (pinfunction "ID3_P$8") (pintype "bidirectional"))
      (node (ref "GPU") (pin "P$6") (pinfunction "PA9_P$6") (pintype "bidirectional"))
    )
    (net (code "39") (name "LEFT") (class "Default")
      (node (ref "IC3") (pin "3") (pinfunction "D1_3") (pintype "input"))
      (node (ref "LEFT") (pin "3") (pinfunction "2_3") (pintype "passive"))
      (node (ref "R66") (pin "1") (pinfunction "1_1") (pintype "passive"))
    )
    (net (code "40") (name "Net-(CPU-PA8)") (class "Default")
      (node (ref "CPU") (pin "P$5") (pinfunction "PA8_P$5") (pintype "bidirectional"))
      (node (ref "R23") (pin "2") (pinfunction "2_2") (pintype "passive"))
    )
    (net (code "41") (name "Net-(CPU-PA9)") (class "Default")
      (node (ref "CPU") (pin "P$6") (pinfunction "PA9_P$6") (pintype "bidirectional"))
      (node (ref "R21") (pin "2") (pinfunction "2_2") (pintype "passive"))
    )
    (net (code "42") (name "Net-(CPU-PA10)") (class "Default")
      (node (ref "CPU") (pin "P$7") (pinfunction "PA10_P$7") (pintype "bidirectional"))
      (node (ref "R22") (pin "2") (pinfunction "2_2") (pintype "passive"))
    )
    (net (code "43") (name "Net-(CPU-PA11)") (class "Default")
      (node (ref "CPU") (pin "P$8") (pinfunction "PA11_P$8") (pintype "bidirectional"))
      (node (ref "R24") (pin "2") (pinfunction "2_2") (pintype "passive"))
    )
    (net (code "44") (name "Net-(CPU-PA12)") (class "Default")
      (node (ref "CPU") (pin "P$9") (pinfunction "PA12_P$9") (pintype "bidirectional"))
      (node (ref "R25") (pin "2") (pinfunction "2_2") (pintype "passive"))
    )
    (net (code "45") (name "Net-(IC1A-I0)") (class "Default")
      (node (ref "COUNTER") (pin "4") (pinfunction "4_4") (pintype "passive"))
      (node (ref "IC1") (pin "2") (pinfunction "I0_2") (pintype "input"))
      (node (ref "IC1") (pin "3") (pinfunction "I1_3") (pintype "input"))
      (node (ref "IC2") (pin "7") (pinfunction "G_7") (pintype "input"))
      (node (ref "IC4") (pin "3") (pinfunction "QD_3") (pintype "tri_state"))
    )
    (net (code "46") (name "Net-(IC1A-O)") (class "Default")
      (node (ref "IC1") (pin "1") (pinfunction "O_1") (pintype "output"))
      (node (ref "IC3") (pin "7") (pinfunction "G_7") (pintype "input"))
    )
    (net (code "47") (name "Net-(IC1B-I0)") (class "Default")
      (node (ref "IC1") (pin "5") (pinfunction "I0_5") (pintype "input"))
      (node (ref "IC2") (pin "5") (pinfunction "Y_5") (pintype "output"))
    )
    (net (code "48") (name "Net-(IC1B-I1)") (class "Default")
      (node (ref "IC1") (pin "6") (pinfunction "I1_6") (pintype "input"))
      (node (ref "IC3") (pin "5") (pinfunction "Y_5") (pintype "output"))
    )
    (net (code "49") (name "Net-(IC1B-O)") (class "Default")
      (node (ref "IC1") (pin "4") (pinfunction "O_4") (pintype "output"))
      (node (ref "IC1") (pin "8") (pinfunction "I0_8") (pintype "input"))
      (node (ref "IC1") (pin "9") (pinfunction "I1_9") (pintype "input"))
    )
    (net (code "50") (name "Net-(IC2A-A)") (class "Default")
      (node (ref "COUNTER") (pin "3") (pinfunction "3_3") (pintype "passive"))
      (node (ref "IC2") (pin "11") (pinfunction "A_11") (pintype "input"))
      (node (ref "IC3") (pin "9") (pinfunction "C_9") (pintype "input"))
      (node (ref "IC4") (pin "2") (pinfunction "QC_2") (pintype "tri_state"))
    )
    (net (code "51") (name "Net-(IC2A-B)") (class "Default")
      (node (ref "COUNTER") (pin "2") (pinfunction "2_2") (pintype "passive"))
      (node (ref "IC2") (pin "10") (pinfunction "B_10") (pintype "input"))
      (node (ref "IC3") (pin "10") (pinfunction "B_10") (pintype "input"))
      (node (ref "IC4") (pin "1") (pinfunction "QB_1") (pintype "tri_state"))
    )
    (net (code "52") (name "Net-(IC2A-C)") (class "Default")
      (node (ref "COUNTER") (pin "1") (pinfunction "1_1") (pintype "passive"))
      (node (ref "IC2") (pin "9") (pinfunction "C_9") (pintype "input"))
      (node (ref "IC3") (pin "11") (pinfunction "A_11") (pintype "input"))
      (node (ref "IC4") (pin "15") (pinfunction "QA_15") (pintype "tri_state"))
    )
    (net (code "53") (name "Net-(LED1-PadA)") (class "Default")
      (node (ref "LED1") (pin "A") (pinfunction "A_A") (pintype "passive"))
      (node (ref "R5") (pin "2") (pinfunction "2_2") (pintype "passive"))
    )
    (net (code "54") (name "Net-(LED2-PadA)") (class "Default")
      (node (ref "LED2") (pin "A") (pinfunction "A_A") (pintype "passive"))
      (node (ref "R26") (pin "2") (pinfunction "2_2") (pintype "passive"))
    )
    (net (code "55") (name "Net-(LED3-PadA)") (class "Default")
      (node (ref "LED3") (pin "A") (pinfunction "A_A") (pintype "passive"))
      (node (ref "R28") (pin "1") (pinfunction "1_1") (pintype "passive"))
    )
    (net (code "56") (name "Net-(POWERIN-VCC)") (class "Default")
      (node (ref "POWERIN") (pin "1") (pinfunction "VCC_1") (pintype "power_in"))
      (node (ref "S1") (pin "1") (pinfunction "O_1") (pintype "passive"))
    )
    (net (code "57") (name "Net-(R6-Pad2)") (class "Default")
      (node (ref "R6") (pin "2") (pinfunction "2_2") (pintype "passive"))
      (node (ref "R7") (pin "1") (pinfunction "1_1") (pintype "passive"))
    )
    (net (code "58") (name "Net-(R11-Pad2)") (class "Default")
      (node (ref "R11") (pin "2") (pinfunction "2_2") (pintype "passive"))
      (node (ref "R12") (pin "1") (pinfunction "1_1") (pintype "passive"))
    )
    (net (code "59") (name "Net-(R16-Pad2)") (class "Default")
      (node (ref "R16") (pin "2") (pinfunction "2_2") (pintype "passive"))
      (node (ref "R17") (pin "1") (pinfunction "1_1") (pintype "passive"))
    )
    (net (code "60") (name "PA15_GPU") (class "Default")
      (node (ref "GPU") (pin "P$10") (pinfunction "PA15_P$10") (pintype "bidirectional"))
    )
    (net (code "61") (name "PC13_CPU") (class "Default")
      (node (ref "CPU") (pin "P$39") (pinfunction "PC13_P$39") (pintype "bidirectional"))
    )
    (net (code "62") (name "PC13_GPU") (class "Default")
      (node (ref "GPU") (pin "P$39") (pinfunction "PC13_P$39") (pintype "bidirectional"))
    )
    (net (code "63") (name "PC14_GPU") (class "Default")
      (node (ref "GPU") (pin "P$38") (pinfunction "PC14_P$38") (pintype "bidirectional"))
      (node (ref "JP5") (pin "2") (pinfunction "2_2") (pintype "passive"))
      (node (ref "R27") (pin "1") (pinfunction "1_1") (pintype "passive"))
    )
    (net (code "64") (name "PC14_GPU2") (class "Default")
      (node (ref "GPU") (pin "P$4") (pinfunction "PB15_P$4") (pintype "bidirectional"))
      (node (ref "JP6") (pin "2") (pinfunction "2_2") (pintype "passive"))
      (node (ref "R29") (pin "1") (pinfunction "1_1") (pintype "passive"))
    )
    (net (code "65") (name "RED_LSP") (class "Default")
      (node (ref "GPU") (pin "P$25") (pinfunction "PB11_P$25") (pintype "bidirectional"))
      (node (ref "R6") (pin "1") (pinfunction "1_1") (pintype "passive"))
    )
    (net (code "66") (name "RED_MMSP") (class "Default")
      (node (ref "GPU") (pin "P$26") (pinfunction "PB10_P$26") (pintype "bidirectional"))
      (node (ref "R8") (pin "1") (pinfunction "1_1") (pintype "passive"))
    )
    (net (code "67") (name "RED_MSP") (class "Default")
      (node (ref "GPU") (pin "P$27") (pinfunction "PB1_P$27") (pintype "bidirectional"))
      (node (ref "R9") (pin "1") (pinfunction "1_1") (pintype "passive"))
    )
    (net (code "68") (name "RESET_CPU") (class "Default")
      (node (ref "CPU") (pin "P$24") (pinfunction "RESET_P$24") (pintype "bidirectional"))
    )
    (net (code "69") (name "RESET_GPU") (class "Default")
      (node (ref "GPU") (pin "P$24") (pinfunction "RESET_P$24") (pintype "bidirectional"))
    )
    (net (code "70") (name "RIGHT") (class "Default")
      (node (ref "IC3") (pin "4") (pinfunction "D0_4") (pintype "input"))
      (node (ref "R65") (pin "1") (pinfunction "1_1") (pintype "passive"))
      (node (ref "RIGHT") (pin "3") (pinfunction "2_3") (pintype "passive"))
    )
    (net (code "71") (name "SDCLK") (class "Default")
      (node (ref "CPU") (pin "P$2") (pinfunction "PB13_P$2") (pintype "bidirectional"))
      (node (ref "SD-CARD") (pin "5") (pinfunction "CLK_5") (pintype "bidirectional"))
    )
    (net (code "72") (name "SDCMD") (class "Default")
      (node (ref "CPU") (pin "P$4") (pinfunction "PB15_P$4") (pintype "bidirectional"))
      (node (ref "SD-CARD") (pin "2") (pinfunction "CMD_2") (pintype "bidirectional"))
    )
    (net (code "73") (name "SDHP") (class "Default")
      (node (ref "CPU") (pin "P$38") (pinfunction "PC14_P$38") (pintype "bidirectional"))
      (node (ref "R54") (pin "1") (pinfunction "1_1") (pintype "passive"))
      (node (ref "SD-CARD") (pin "CD") (pinfunction "CD_CD") (pintype "bidirectional"))
    )
    (net (code "74") (name "SDIN") (class "Default")
      (node (ref "CPU") (pin "P$1") (pinfunction "PB12_P$1") (pintype "bidirectional"))
      (node (ref "SD-CARD") (pin "1") (pinfunction "CD/DAT3_1") (pintype "bidirectional"))
    )
    (net (code "75") (name "SDOUT") (class "Default")
      (node (ref "CPU") (pin "P$3") (pinfunction "PB14_P$3") (pintype "bidirectional"))
      (node (ref "R56") (pin "1") (pinfunction "1_1") (pintype "passive"))
      (node (ref "SD-CARD") (pin "7") (pinfunction "DAT0_7") (pintype "bidirectional"))
    )
    (net (code "76") (name "SELECT") (class "Default")
      (node (ref "IC3") (pin "15") (pinfunction "D4_15") (pintype "input"))
      (node (ref "R61") (pin "1") (pinfunction "1_1") (pintype "passive"))
      (node (ref "SELECT") (pin "3") (pinfunction "2_3") (pintype "passive"))
    )
    (net (code "77") (name "SIG0_1") (class "Default")
      (node (ref "CPU") (pin "P$36") (pinfunction "PA0_P$36") (pintype "bidirectional"))
      (node (ref "EXTENSION1") (pin "P$11") (pinfunction "SIG0_P$11") (pintype "bidirectional"))
    )
    (net (code "78") (name "SIG0_2") (class "Default")
      (node (ref "CPU") (pin "P$28") (pinfunction "PB0_P$28") (pintype "bidirectional"))
      (node (ref "EXTENSION2") (pin "P$11") (pinfunction "SIG0_P$11") (pintype "bidirectional"))
    )
    (net (code "79") (name "SIG1_1") (class "Default")
      (node (ref "CPU") (pin "P$35") (pinfunction "PA1_P$35") (pintype "bidirectional"))
      (node (ref "EXTENSION1") (pin "P$12") (pinfunction "SIG1_P$12") (pintype "bidirectional"))
    )
    (net (code "80") (name "SIG1_2") (class "Default")
      (node (ref "CPU") (pin "P$27") (pinfunction "PB1_P$27") (pintype "bidirectional"))
      (node (ref "EXTENSION2") (pin "P$12") (pinfunction "SIG1_P$12") (pintype "bidirectional"))
    )
    (net (code "81") (name "SIG2_1") (class "Default")
      (node (ref "CPU") (pin "P$34") (pinfunction "PA2_P$34") (pintype "bidirectional"))
      (node (ref "EXTENSION1") (pin "P$13") (pinfunction "SIG2_P$13") (pintype "bidirectional"))
    )
    (net (code "82") (name "SIG2_2") (class "Default")
      (node (ref "CPU") (pin "P$26") (pinfunction "PB10_P$26") (pintype "bidirectional"))
      (node (ref "EXTENSION2") (pin "P$13") (pinfunction "SIG2_P$13") (pintype "bidirectional"))
    )
    (net (code "83") (name "SIG3_1") (class "Default")
      (node (ref "CPU") (pin "P$33") (pinfunction "PA3_P$33") (pintype "bidirectional"))
      (node (ref "EXTENSION1") (pin "P$14") (pinfunction "SIG3_P$14") (pintype "bidirectional"))
    )
    (net (code "84") (name "SIG3_2") (class "Default")
      (node (ref "CPU") (pin "P$25") (pinfunction "PB11_P$25") (pintype "bidirectional"))
      (node (ref "EXTENSION2") (pin "P$14") (pinfunction "SIG3_P$14") (pintype "bidirectional"))
    )
    (net (code "85") (name "SIG4_1") (class "Default")
      (node (ref "CPU") (pin "P$32") (pinfunction "PA4_P$32") (pintype "bidirectional"))
      (node (ref "EXTENSION1") (pin "P$15") (pinfunction "SIG4_P$15") (pintype "bidirectional"))
    )
    (net (code "86") (name "SIG4_2") (class "Default")
      (node (ref "CPU") (pin "P$17") (pinfunction "PB9_P$17") (pintype "bidirectional"))
      (node (ref "EXTENSION2") (pin "P$15") (pinfunction "SIG4_P$15") (pintype "bidirectional"))
    )
    (net (code "87") (name "SIG5_1") (class "Default")
      (node (ref "CPU") (pin "P$31") (pinfunction "PA5_P$31") (pintype "bidirectional"))
      (node (ref "EXTENSION1") (pin "P$16") (pinfunction "SIG5_P$16") (pintype "bidirectional"))
    )
    (net (code "88") (name "SIG5_2") (class "Default")
      (node (ref "CPU") (pin "P$16") (pinfunction "PB8_P$16") (pintype "bidirectional"))
      (node (ref "EXTENSION2") (pin "P$16") (pinfunction "SIG5_P$16") (pintype "bidirectional"))
    )
    (net (code "89") (name "SIG6_1") (class "Default")
      (node (ref "CPU") (pin "P$30") (pinfunction "PA6_P$30") (pintype "bidirectional"))
      (node (ref "EXTENSION1") (pin "P$17") (pinfunction "SIG6_P$17") (pintype "bidirectional"))
    )
    (net (code "90") (name "SIG6_2") (class "Default")
      (node (ref "CPU") (pin "P$15") (pinfunction "PB7_P$15") (pintype "bidirectional"))
      (node (ref "EXTENSION2") (pin "P$17") (pinfunction "SIG6_P$17") (pintype "bidirectional"))
    )
    (net (code "91") (name "SIG7_1") (class "Default")
      (node (ref "CPU") (pin "P$29") (pinfunction "PA7_P$29") (pintype "bidirectional"))
      (node (ref "EXTENSION1") (pin "P$18") (pinfunction "SIG7_P$18") (pintype "bidirectional"))
    )
    (net (code "92") (name "SIG7_2") (class "Default")
      (node (ref "CPU") (pin "P$14") (pinfunction "PB6_P$14") (pintype "bidirectional"))
      (node (ref "EXTENSION2") (pin "P$18") (pinfunction "SIG7_P$18") (pintype "bidirectional"))
    )
    (net (code "93") (name "START") (class "Default")
      (node (ref "IC3") (pin "14") (pinfunction "D5_14") (pintype "input"))
      (node (ref "R62") (pin "1") (pinfunction "1_1") (pintype "passive"))
      (node (ref "START") (pin "3") (pinfunction "2_3") (pintype "passive"))
    )
    (net (code "94") (name "UP") (class "Default")
      (node (ref "IC3") (pin "1") (pinfunction "D3_1") (pintype "input"))
      (node (ref "R68") (pin "1") (pinfunction "1_1") (pintype "passive"))
      (node (ref "UP") (pin "3") (pinfunction "2_3") (pintype "passive"))
    )
    (net (code "95") (name "VBAT_CPU") (class "Default")
      (node (ref "CPU") (pin "P$40") (pinfunction "VBAT_P$40") (pintype "bidirectional"))
    )
    (net (code "96") (name "VBAT_GPU") (class "Default")
      (node (ref "GPU") (pin "P$40") (pinfunction "VBAT_P$40") (pintype "bidirectional"))
    )
    (net (code "97") (name "VCC") (class "Default")
      (node (ref "A") (pin "1") (pinfunction "1_1") (pintype "passive"))
      (node (ref "B") (pin "1") (pinfunction "1_1") (pintype "passive"))
      (node (ref "C10") (pin "1") (pinfunction "1_1") (pintype "passive"))
      (node (ref "C11") (pin "1") (pinfunction "1_1") (pintype "passive"))
      (node (ref "C7") (pin "1") (pinfunction "1_1") (pintype "passive"))
      (node (ref "C8") (pin "1") (pinfunction "1_1") (pintype "passive"))
      (node (ref "C9") (pin "1") (pinfunction "1_1") (pintype "passive"))
      (node (ref "CONTROLLERIN") (pin "1") (pinfunction "VCC_1") (pintype "power_in"))
      (node (ref "DOWN") (pin "1") (pinfunction "1_1") (pintype "passive"))
      (node (ref "IC1") (pin "14") (pinfunction "VCC_14") (pintype "power_in"))
      (node (ref "IC2") (pin "12") (pinfunction "D7_12") (pintype "input"))
      (node (ref "IC2") (pin "16") (pinfunction "VCC_16") (pintype "power_in"))
      (node (ref "IC3") (pin "16") (pinfunction "VCC_16") (pintype "power_in"))
      (node (ref "IC4") (pin "10") (pinfunction "CCLR_10") (pintype "input"))
      (node (ref "IC4") (pin "16") (pinfunction "VCC_16") (pintype "power_in"))
      (node (ref "JP2") (pin "1") (pinfunction "1_1") (pintype "passive"))
      (node (ref "LEFT") (pin "1") (pinfunction "1_1") (pintype "passive"))
      (node (ref "R26") (pin "1") (pinfunction "1_1") (pintype "passive"))
      (node (ref "RIGHT") (pin "1") (pinfunction "1_1") (pintype "passive"))
      (node (ref "SELECT") (pin "1") (pinfunction "1_1") (pintype "passive"))
      (node (ref "START") (pin "1") (pinfunction "1_1") (pintype "passive"))
      (node (ref "UP") (pin "1") (pinfunction "1_1") (pintype "passive"))
    )
    (net (code "98") (name "VGA_BLUE") (class "Default")
      (node (ref "R17") (pin "2") (pinfunction "2_2") (pintype "passive"))
      (node (ref "R18") (pin "2") (pinfunction "2_2") (pintype "passive"))
      (node (ref "R19") (pin "2") (pinfunction "2_2") (pintype "passive"))
      (node (ref "R20") (pin "2") (pinfunction "2_2") (pintype "passive"))
      (node (ref "VGA") (pin "3") (pinfunction "3_3") (pintype "bidirectional"))
    )
    (net (code "99") (name "VGA_GREEN") (class "Default")
      (node (ref "R12") (pin "2") (pinfunction "2_2") (pintype "passive"))
      (node (ref "R13") (pin "2") (pinfunction "2_2") (pintype "passive"))
      (node (ref "R14") (pin "2") (pinfunction "2_2") (pintype "passive"))
      (node (ref "R15") (pin "2") (pinfunction "2_2") (pintype "passive"))
      (node (ref "VGA") (pin "2") (pinfunction "2_2") (pintype "bidirectional"))
    )
    (net (code "100") (name "VGA_RED") (class "Default")
      (node (ref "R10") (pin "2") (pinfunction "2_2") (pintype "passive"))
      (node (ref "R7") (pin "2") (pinfunction "2_2") (pintype "passive"))
      (node (ref "R8") (pin "2") (pinfunction "2_2") (pintype "passive"))
      (node (ref "R9") (pin "2") (pinfunction "2_2") (pintype "passive"))
      (node (ref "VGA") (pin "1") (pinfunction "1_1") (pintype "bidirectional"))
    )
    (net (code "101") (name "VSYNC") (class "Default")
      (node (ref "GPU") (pin "P$28") (pinfunction "PB0_P$28") (pintype "bidirectional"))
      (node (ref "VGA") (pin "14") (pinfunction "14_14") (pintype "bidirectional"))
    )
    (net (code "102") (name "unconnected-(EXTENSION1-P$1-PadP$10)") (class "Default")
      (node (ref "EXTENSION1") (pin "P$10") (pinfunction "P$1_P$10") (pintype "bidirectional"))
    )
    (net (code "103") (name "unconnected-(EXTENSION1-P$2-PadP$19)") (class "Default")
      (node (ref "EXTENSION1") (pin "P$19") (pinfunction "P$2_P$19") (pintype "bidirectional"))
    )
    (net (code "104") (name "unconnected-(EXTENSION1-P$11-PadP$20)") (class "Default")
      (node (ref "EXTENSION1") (pin "P$20") (pinfunction "P$11_P$20") (pintype "bidirectional"))
    )
    (net (code "105") (name "unconnected-(EXTENSION2-P$1-PadP$10)") (class "Default")
      (node (ref "EXTENSION2") (pin "P$10") (pinfunction "P$1_P$10") (pintype "bidirectional"))
    )
    (net (code "106") (name "unconnected-(EXTENSION2-P$2-PadP$19)") (class "Default")
      (node (ref "EXTENSION2") (pin "P$19") (pinfunction "P$2_P$19") (pintype "bidirectional"))
    )
    (net (code "107") (name "unconnected-(EXTENSION2-P$11-PadP$20)") (class "Default")
      (node (ref "EXTENSION2") (pin "P$20") (pinfunction "P$11_P$20") (pintype "bidirectional"))
    )
    (net (code "108") (name "unconnected-(IC1D-O-Pad13)") (class "Default")
      (node (ref "IC1") (pin "13") (pinfunction "O_13") (pintype "output"))
    )
    (net (code "109") (name "unconnected-(IC2A-W-Pad6)") (class "Default")
      (node (ref "IC2") (pin "6") (pinfunction "W_6") (pintype "output"))
    )
    (net (code "110") (name "unconnected-(IC3A-W-Pad6)") (class "Default")
      (node (ref "IC3") (pin "6") (pinfunction "W_6") (pintype "output"))
    )
    (net (code "111") (name "unconnected-(IC4A-QE-Pad4)") (class "Default")
      (node (ref "IC4") (pin "4") (pinfunction "QE_4") (pintype "tri_state"))
    )
    (net (code "112") (name "unconnected-(IC4A-QF-Pad5)") (class "Default")
      (node (ref "IC4") (pin "5") (pinfunction "QF_5") (pintype "tri_state"))
    )
    (net (code "113") (name "unconnected-(IC4A-QG-Pad6)") (class "Default")
      (node (ref "IC4") (pin "6") (pinfunction "QG_6") (pintype "tri_state"))
    )
    (net (code "114") (name "unconnected-(IC4A-QH-Pad7)") (class "Default")
      (node (ref "IC4") (pin "7") (pinfunction "QH_7") (pintype "tri_state"))
    )
    (net (code "115") (name "unconnected-(IC4A-RCO-Pad9)") (class "Default")
      (node (ref "IC4") (pin "9") (pinfunction "RCO_9") (pintype "output"))
    )
    (net (code "116") (name "unconnected-(POWERIN-D+-Pad3)") (class "Default")
      (node (ref "POWERIN") (pin "3") (pinfunction "D+_3") (pintype "bidirectional"))
    )
    (net (code "117") (name "unconnected-(POWERIN-D--Pad2)") (class "Default")
      (node (ref "POWERIN") (pin "2") (pinfunction "D-_2") (pintype "bidirectional"))
    )
    (net (code "118") (name "unconnected-(S1-S-Pad3)") (class "Default")
      (node (ref "S1") (pin "3") (pinfunction "S_3") (pintype "passive"))
    )
    (net (code "119") (name "unconnected-(SD-CARD-DAT1-Pad8)") (class "Default")
      (node (ref "SD-CARD") (pin "8") (pinfunction "DAT1_8") (pintype "bidirectional"))
    )
    (net (code "120") (name "unconnected-(SD-CARD-DAT2-Pad9)") (class "Default")
      (node (ref "SD-CARD") (pin "9") (pinfunction "DAT2_9") (pintype "bidirectional"))
    )
    (net (code "121") (name "unconnected-(SD-CARD-PadWP)") (class "Default")
      (node (ref "SD-CARD") (pin "WP") (pinfunction "WP_WP") (pintype "bidirectional"))
    )
    (net (code "122") (name "unconnected-(VGA-Pad4)") (class "Default")
      (node (ref "VGA") (pin "4") (pinfunction "4_4") (pintype "bidirectional"))
    )
    (net (code "123") (name "unconnected-(VGA-Pad9)") (class "Default")
      (node (ref "VGA") (pin "9") (pinfunction "9_9") (pintype "bidirectional"))
    )
    (net (code "124") (name "unconnected-(VGA-Pad10)") (class "Default")
      (node (ref "VGA") (pin "10") (pinfunction "10_10") (pintype "bidirectional"))
    )
    (net (code "125") (name "unconnected-(VGA-Pad12)") (class "Default")
      (node (ref "VGA") (pin "12") (pinfunction "12_12") (pintype "bidirectional"))
    )
    (net (code "126") (name "unconnected-(VGA-Pad15)") (class "Default")
      (node (ref "VGA") (pin "15") (pinfunction "15_15") (pintype "bidirectional"))
    )
    (net (code "127") (name "unconnected-(VGA-PadMH1)") (class "Default")
      (node (ref "VGA") (pin "MH1") (pinfunction "MH1_MH1") (pintype "bidirectional"))
    )
    (net (code "128") (name "unconnected-(VGA-PadMH2)") (class "Default")
      (node (ref "VGA") (pin "MH2") (pinfunction "MH2_MH2") (pintype "bidirectional"))
    )
  )
)
